# HV_power_supply.net
KiCad netlist of a schematic drawn in Altium Designer
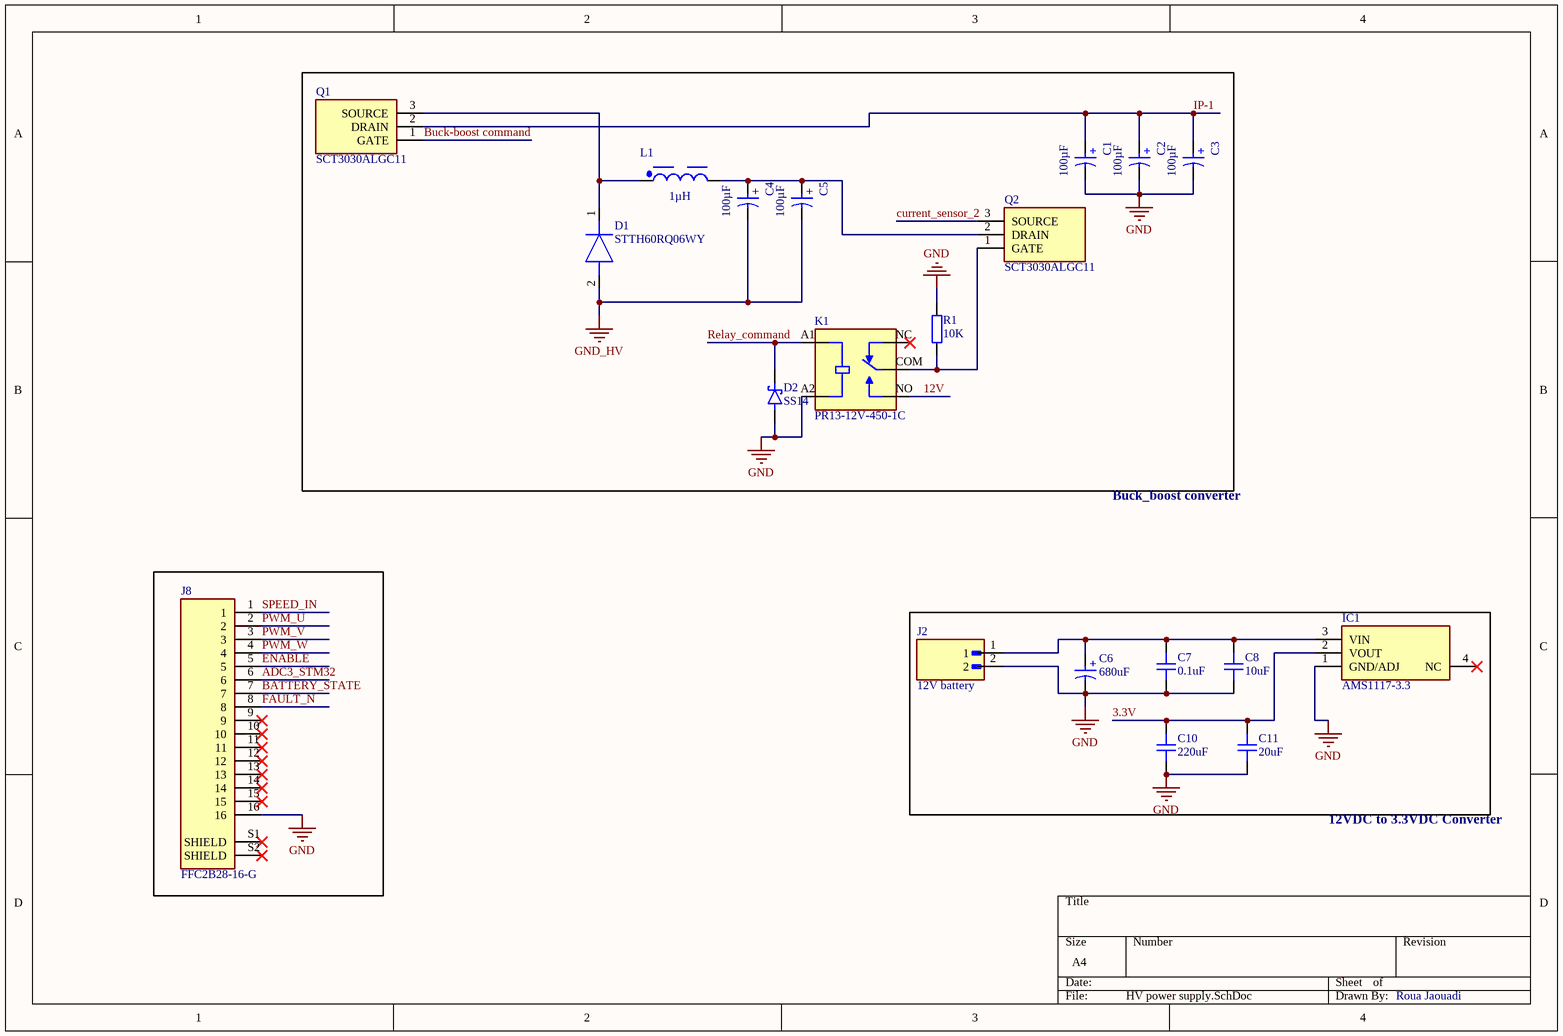
[diagram p0: HV power supply.SchDoc]

(export (version "E")
  (design (tool "Eeschema 10.0.6"))
  (components
    (comp (ref "C1")
      (value "100µF")
      (footprint "WCAP-AT1H:WCAP-AT1H_D16H35.5")
      (description "WCAP-AT1H Aluminum Electrolytic Capacitor, Radial, D16 x H35.5mm, 100µF, 450V")
      (fields
        (field (name "MANUFACTURER PART NUMBER") "860241480001")
        (field (name "MANUFACTURER") "Wurth Elektronik")
      )
      (libsource (lib "WCAP-AT1H") (part "860241480001"))
    )
    (comp (ref "C2")
      (value "100µF")
      (footprint "WCAP-AT1H:WCAP-AT1H_D16H35.5")
      (description "WCAP-AT1H Aluminum Electrolytic Capacitor, Radial, D16 x H35.5mm, 100µF, 450V")
      (fields
        (field (name "MANUFACTURER PART NUMBER") "860241480001")
        (field (name "MANUFACTURER") "Wurth Elektronik")
      )
      (libsource (lib "WCAP-AT1H") (part "860241480001"))
    )
    (comp (ref "C3")
      (value "100µF")
      (footprint "WCAP-AT1H:WCAP-AT1H_D16H35.5")
      (description "WCAP-AT1H Aluminum Electrolytic Capacitor, Radial, D16 x H35.5mm, 100µF, 450V")
      (fields
        (field (name "MANUFACTURER PART NUMBER") "860241480001")
        (field (name "MANUFACTURER") "Wurth Elektronik")
      )
      (libsource (lib "WCAP-AT1H") (part "860241480001"))
    )
    (comp (ref "C4")
      (value "100µF")
      (footprint "WCAP-AT1H:WCAP-AT1H_D16H35.5")
      (description "WCAP-AT1H Aluminum Electrolytic Capacitor, Radial, D16 x H35.5mm, 100µF, 450V")
      (fields
        (field (name "MANUFACTURER PART NUMBER") "860241480001")
        (field (name "MANUFACTURER") "Wurth Elektronik")
      )
      (libsource (lib "WCAP-AT1H") (part "860241480001"))
    )
    (comp (ref "C5")
      (value "100µF")
      (footprint "WCAP-AT1H:WCAP-AT1H_D16H35.5")
      (description "WCAP-AT1H Aluminum Electrolytic Capacitor, Radial, D16 x H35.5mm, 100µF, 450V")
      (fields
        (field (name "MANUFACTURER PART NUMBER") "860241480001")
        (field (name "MANUFACTURER") "Wurth Elektronik")
      )
      (libsource (lib "WCAP-AT1H") (part "860241480001"))
    )
    (comp (ref "C6")
      (value "680uF")
      (footprint "WCAP-ATG8_D8H16")
      (description "WCAP-ATG8 Aluminum Electrolytic Capacitor, Radial, THT, D8 x H16mm, 680uF, 16V")
      (fields
        (field (name "MANUFACTURER PART NUMBER") "860010374014")
        (field (name "MANUFACTURER") "Wurth Elektronik")
      )
      (libsource (lib "Schlib1") (part "860010374014"))
    )
    (comp (ref "C7")
      (value "0.1uF")
      (footprint "CAP_0603")
      (description "Capacitor SMD 0603")
      (libsource (lib "Schematic-Lib-PhilsLab") (part "CAP_0603"))
    )
    (comp (ref "C8")
      (value "10uF")
      (footprint "CAP_1206")
      (description "Capacitor SMD 1206")
      (libsource (lib "Schematic-Lib-PhilsLab") (part "CAP_1206"))
    )
    (comp (ref "C10")
      (value "220uF")
      (footprint "CAP-EL-NP-5MM")
      (description "Capacitor SMD Electrolytic Non-Polarised 5mm Diameter")
      (fields (field (name "MANUFACTURER") "Nichicon"))
      (libsource (lib "Schematic-Lib-PhilsLab") (part "CAP_EL_NP_5MM"))
    )
    (comp (ref "C11")
      (value "20uF")
      (footprint "CAP_1206")
      (description "Capacitor SMD 1206")
      (libsource (lib "Schematic-Lib-PhilsLab") (part "CAP_1206"))
    )
    (comp (ref "D1")
      (value "STTH60RQ06WY")
      (footprint "SamacSys:TO1090P515X1560X2445-2P")
      (description "Diode")
      (fields (field (name "MOUSER PART NUMBER") "511-STTH60RQ06WY"))
      (libsource (lib "*") (part "STTH60RQ06WY"))
    )
    (comp (ref "D2")
      (value "SS14")
      (footprint "DIOM4325X250N:DIOM4325X250N")
      (description "1A, 40V, Schottky Rectifier")
      (fields (field (name "MF") "Taiwan Semiconductor"))
      (libsource (lib "SS14") (part "SS14"))
    )
    (comp (ref "IC1")
      (value "AMS1117-3.3")
      (footprint "SamacSys:SOT229P700X180-4N")
      (description "Integrated Circuit")
      (libsource (lib "SamacSys") (part "AMS1117-3.3"))
    )
    (comp (ref "J2")
      (value "12V battery")
      (footprint "JST_S2B-XH-A(LF)(SN):JST_S2B-XH-A(LF)(SN)")
      (description "Connector Header Through Hole, Right Angle 2 position 0.098 (2.50mm)")
      (fields (field (name "MF") "JST Sales") (field (name "MP") "S2B-XH-A(LF)(SN)"))
      (libsource (lib "S2B-XH-A(LF)(SN)") (part "S2B-XH-A(LF)(SN)"))
    )
    (comp (ref "J8")
      (value "FFC2B28-16-G")
      (footprint "GCT_FFC2B28-16-G:GCT_FFC2B28-16-G")
      (description "16 Position FFC, FPC Connector Contacts, Top and Bottom 0.020 (0.50mm) Surface Mount, Right Angle")
      (fields (field (name "MF") "Global Connector Technology"))
      (libsource (lib "FFC2B28-16-G") (part "FFC2B28-16-G"))
    )
    (comp (ref "K1")
      (value "PR13-12V-450-1C")
      (footprint "RELAY_PR13-12V-450-1C:RELAY_PR13-12V-450-1C")
      (description "19 x 15.5 x 15.8 mm, 12 V, 10 A, SPDT (1 Form C), Power Relay")
      (fields (field (name "MF") "Same Sky"))
      (libsource (lib "PR13-12V-450-1C") (part "PR13-12V-450-1C"))
    )
    (comp (ref "L1")
      (value "1µH")
      (footprint "WE-HCFT_2504_7443762504010")
      (description "WE-HCFT THT High Current Inductor, size 2504, 1µH, 39A")
      (fields
        (field (name "MANUFACTURER PART NUMBER") "7443762504010")
        (field (name "MANUFACTURER") "Wurth Elektronik")
      )
      (libsource (lib "WE-HCFT") (part "7443762504010"))
    )
    (comp (ref "Q1")
      (value "SCT3030ALGC11")
      (footprint "SamacSys:TO545P515X1600X2535-3P")
      (description "Transistor")
      (fields (field (name "MOUSER PART NUMBER") "755-SCT3030ALGC11"))
      (libsource (lib "") (part "SCT3030ALGC11_1"))
    )
    (comp (ref "Q2")
      (value "SCT3030ALGC11")
      (footprint "SamacSys:TO545P515X1600X2535-3P")
      (description "Transistor")
      (fields (field (name "MOUSER PART NUMBER") "755-SCT3030ALGC11"))
      (libsource (lib "*") (part "SCT3030ALGC11"))
    )
    (comp (ref "R1")
      (value "10K")
      (footprint "RES_0603")
      (description "Resistor SMD 0603")
      (libsource (lib "Schlib1") (part "RES_0603"))
    )
  )
  (nets
    (net (code "1") (name "/3.3V") (class "Default")
      (node (ref "C10") (pin "1") (pinfunction "1_1") (pintype "passive"))
      (node (ref "C11") (pin "1") (pinfunction "1_1") (pintype "passive"))
      (node (ref "IC1") (pin "2") (pinfunction "VOUT_2") (pintype "passive"))
    )
    (net (code "2") (name "/12V") (class "Default")
      (node (ref "K1") (pin "NO") (pinfunction "NO_NO") (pintype "passive"))
    )
    (net (code "3") (name "/ADC3_STM32") (class "Default")
      (node (ref "J8") (pin "6") (pinfunction "6_6") (pintype "passive"))
    )
    (net (code "4") (name "/BATTERY_STATE") (class "Default")
      (node (ref "J8") (pin "7") (pinfunction "7_7") (pintype "passive"))
    )
    (net (code "5") (name "/Buck-boost command") (class "Default")
      (node (ref "Q1") (pin "1") (pinfunction "GATE_1") (pintype "passive"))
    )
    (net (code "6") (name "/ENABLE") (class "Default")
      (node (ref "J8") (pin "5") (pinfunction "5_5") (pintype "passive"))
    )
    (net (code "7") (name "/FAULT_N") (class "Default")
      (node (ref "J8") (pin "8") (pinfunction "8_8") (pintype "passive"))
    )
    (net (code "8") (name "/IP-1") (class "Default")
      (node (ref "C1") (pin "1") (pinfunction "P_1") (pintype "passive"))
      (node (ref "C2") (pin "1") (pinfunction "P_1") (pintype "passive"))
      (node (ref "C3") (pin "1") (pinfunction "P_1") (pintype "passive"))
      (node (ref "Q1") (pin "2") (pinfunction "DRAIN_2") (pintype "passive"))
    )
    (net (code "9") (name "/PWM_U") (class "Default")
      (node (ref "J8") (pin "2") (pinfunction "2_2") (pintype "passive"))
    )
    (net (code "10") (name "/PWM_V") (class "Default")
      (node (ref "J8") (pin "3") (pinfunction "3_3") (pintype "passive"))
    )
    (net (code "11") (name "/PWM_W") (class "Default")
      (node (ref "J8") (pin "4") (pinfunction "4_4") (pintype "passive"))
    )
    (net (code "12") (name "/Relay_command") (class "Default")
      (node (ref "D2") (pin "C") (pinfunction "K_C") (pintype "passive"))
      (node (ref "K1") (pin "A1") (pinfunction "COIL1_A1") (pintype "passive"))
    )
    (net (code "13") (name "/SPEED_IN") (class "Default")
      (node (ref "J8") (pin "1") (pinfunction "1_1") (pintype "passive"))
    )
    (net (code "14") (name "/current_sensor_2") (class "Default")
      (node (ref "Q2") (pin "3") (pinfunction "SOURCE_3") (pintype "passive"))
    )
    (net (code "15") (name "GND") (class "Default")
      (node (ref "C1") (pin "2") (pinfunction "N_2") (pintype "passive"))
      (node (ref "C10") (pin "2") (pinfunction "2_2") (pintype "passive"))
      (node (ref "C11") (pin "2") (pinfunction "2_2") (pintype "passive"))
      (node (ref "C2") (pin "2") (pinfunction "N_2") (pintype "passive"))
      (node (ref "C3") (pin "2") (pinfunction "N_2") (pintype "passive"))
      (node (ref "C6") (pin "2") (pinfunction "N_2") (pintype "passive"))
      (node (ref "C7") (pin "2") (pinfunction "2_2") (pintype "passive"))
      (node (ref "C8") (pin "2") (pinfunction "2_2") (pintype "passive"))
      (node (ref "D2") (pin "A") (pinfunction "A_A") (pintype "passive"))
      (node (ref "IC1") (pin "1") (pinfunction "GND/ADJ_1") (pintype "passive"))
      (node (ref "J2") (pin "2") (pinfunction "2_2") (pintype "passive"))
      (node (ref "J8") (pin "16") (pinfunction "16_16") (pintype "passive"))
      (node (ref "K1") (pin "A2") (pinfunction "COIL2_A2") (pintype "passive"))
      (node (ref "R1") (pin "1") (pinfunction "1_1") (pintype "passive"))
    )
    (net (code "16") (name "GND_HV") (class "Default")
      (node (ref "C4") (pin "2") (pinfunction "N_2") (pintype "passive"))
      (node (ref "C5") (pin "2") (pinfunction "N_2") (pintype "passive"))
      (node (ref "D1") (pin "2") (pinfunction "A_2") (pintype "passive"))
    )
    (net (code "17") (name "Net-(C4-P)") (class "Default")
      (node (ref "C4") (pin "1") (pinfunction "P_1") (pintype "passive"))
      (node (ref "C5") (pin "1") (pinfunction "P_1") (pintype "passive"))
      (node (ref "L1") (pin "2") (pinfunction "2_2") (pintype "passive"))
      (node (ref "Q2") (pin "2") (pinfunction "DRAIN_2") (pintype "passive"))
    )
    (net (code "18") (name "Net-(C6-P)") (class "Default")
      (node (ref "C6") (pin "1") (pinfunction "P_1") (pintype "passive"))
      (node (ref "C7") (pin "1") (pinfunction "1_1") (pintype "passive"))
      (node (ref "C8") (pin "1") (pinfunction "1_1") (pintype "passive"))
      (node (ref "IC1") (pin "3") (pinfunction "VIN_3") (pintype "passive"))
      (node (ref "J2") (pin "1") (pinfunction "1_1") (pintype "passive"))
    )
    (net (code "19") (name "Net-(D1-K)") (class "Default")
      (node (ref "D1") (pin "1") (pinfunction "K_1") (pintype "passive"))
      (node (ref "L1") (pin "1") (pinfunction "1_1") (pintype "passive"))
      (node (ref "Q1") (pin "3") (pinfunction "SOURCE_3") (pintype "passive"))
    )
    (net (code "20") (name "Net-(Q2-GATE)") (class "Default")
      (node (ref "K1") (pin "COM") (pinfunction "COM_COM") (pintype "passive"))
      (node (ref "Q2") (pin "1") (pinfunction "GATE_1") (pintype "passive"))
      (node (ref "R1") (pin "2") (pinfunction "2_2") (pintype "passive"))
    )
    (net (code "21") (name "unconnected-(IC1-NC-Pad4)") (class "Default")
      (node (ref "IC1") (pin "4") (pinfunction "NC_4") (pintype "passive+no_connect"))
    )
    (net (code "22") (name "unconnected-(J8-Pad9)") (class "Default")
      (node (ref "J8") (pin "9") (pinfunction "9_9") (pintype "passive+no_connect"))
    )
    (net (code "23") (name "unconnected-(J8-Pad10)") (class "Default")
      (node (ref "J8") (pin "10") (pinfunction "10_10") (pintype "passive+no_connect"))
    )
    (net (code "24") (name "unconnected-(J8-Pad11)") (class "Default")
      (node (ref "J8") (pin "11") (pinfunction "11_11") (pintype "passive+no_connect"))
    )
    (net (code "25") (name "unconnected-(J8-Pad12)") (class "Default")
      (node (ref "J8") (pin "12") (pinfunction "12_12") (pintype "passive+no_connect"))
    )
    (net (code "26") (name "unconnected-(J8-Pad13)") (class "Default")
      (node (ref "J8") (pin "13") (pinfunction "13_13") (pintype "passive+no_connect"))
    )
    (net (code "27") (name "unconnected-(J8-Pad14)") (class "Default")
      (node (ref "J8") (pin "14") (pinfunction "14_14") (pintype "passive+no_connect"))
    )
    (net (code "28") (name "unconnected-(J8-Pad15)") (class "Default")
      (node (ref "J8") (pin "15") (pinfunction "15_15") (pintype "passive+no_connect"))
    )
    (net (code "29") (name "unconnected-(J8-SHIELD-PadS1)") (class "Default")
      (node (ref "J8") (pin "S1") (pinfunction "SHIELD_S1") (pintype "passive+no_connect"))
    )
    (net (code "30") (name "unconnected-(J8-SHIELD-PadS2)") (class "Default")
      (node (ref "J8") (pin "S2") (pinfunction "SHIELD_S2") (pintype "passive+no_connect"))
    )
    (net (code "31") (name "unconnected-(K1-PadNC)") (class "Default")
      (node (ref "K1") (pin "NC") (pinfunction "NC_NC") (pintype "passive+no_connect"))
    )
  )
)
